# LED_Driver.net
KiCad netlist of a schematic drawn in Altium Designer
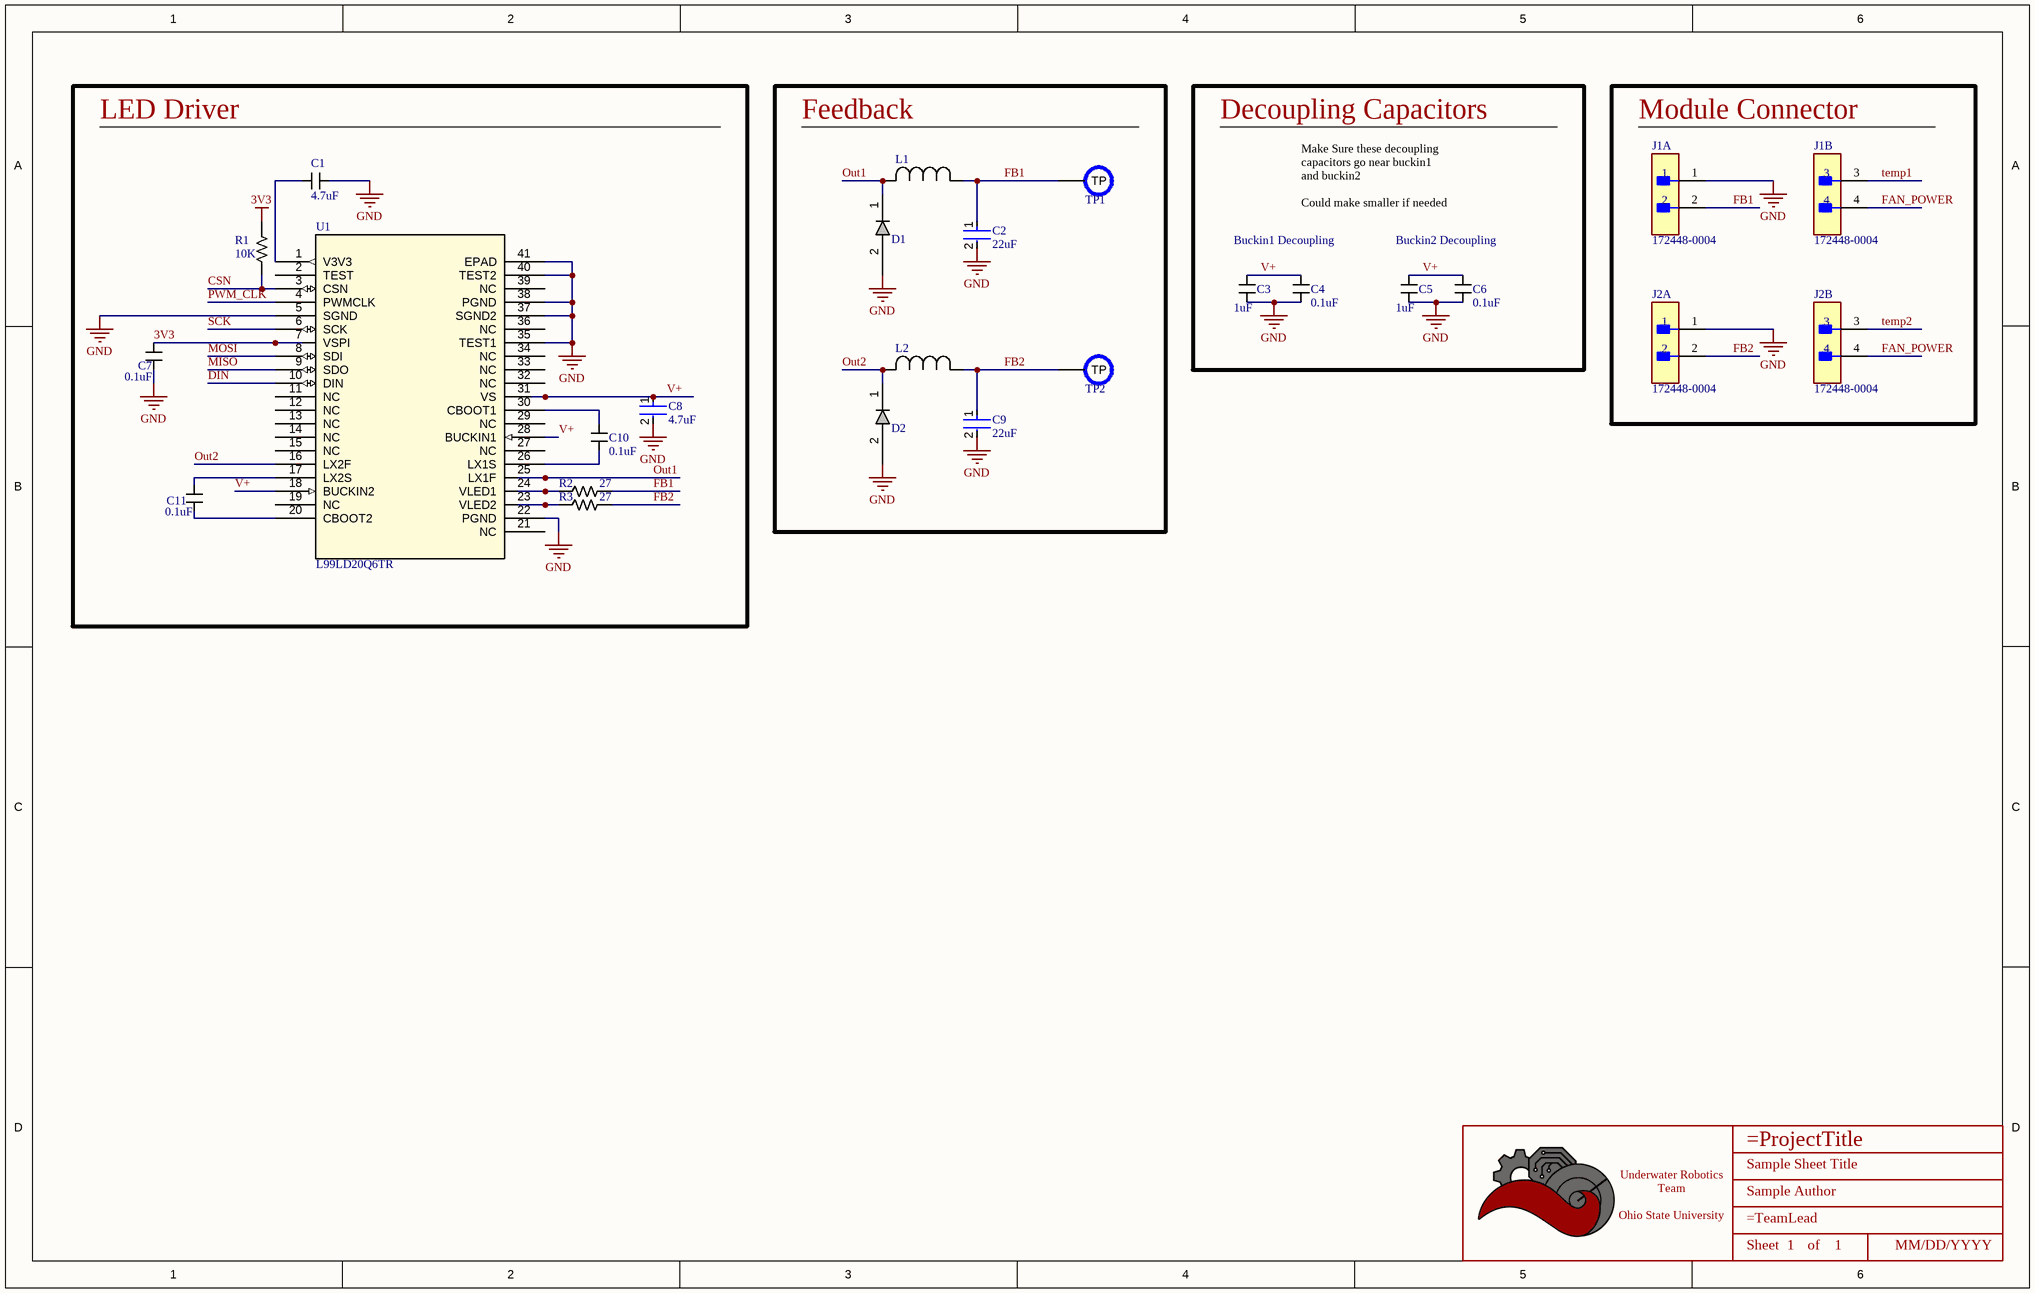
[diagram p0: LED_Driver.SchDoc]

(export (version "E")
  (design (tool "Eeschema 10.0.6"))
  (components
    (comp (ref "*")
      (value "Title_Block")
      (footprint "LOGO")
      (description "UWRT Schematic Title Block Template\r\n\r\nCreated June 2021, Dylan Trainor")
      (libsource (lib "UWRT") (part "Title_Block"))
    )
    (comp (ref "C1")
      (value "4.7uF")
      (footprint "CAPACITOR_0603")
      (description "Cap 4.7uF 6.3V +/-10%\r\nCeramic 0603")
      (fields
        (field (name "TOLERANCE") "+/- 10%")
        (field (name "VOLTAGE") "6.3V")
        (field (name "MADE BY") "Robert Pafford")
      )
      (libsource (lib "Capacitors") (part "CAPACITOR_4.7uF_0603"))
    )
    (comp (ref "C2")
      (value "22uF")
      (footprint "FP-C2012-125-0_2-MFG")
      (description "Multilayer Ceramic Capacitors 22μF ±20% 35V X5R SMD 0805")
      (fields (field (name "TOLERANCE") "20%"))
      (libsource (lib "Altium Content Vault") (part "b4654b650e69147ec39a6b967a45e02"))
    )
    (comp (ref "C3")
      (value "1uF")
      (footprint "CAPACITOR_0603")
      (description "Cap 1uF 25V +/-10%\r\nCeramic 0603")
      (fields
        (field (name "TOLERANCE") "+/- 10%")
        (field (name "VOLTAGE") "16V")
        (field (name "MADE BY") "Flip B")
      )
      (libsource (lib "Capacitors") (part "CAPACITOR_1uF_0603_25V"))
    )
    (comp (ref "C4")
      (value "0.1uF")
      (footprint "CAPACITOR_0603")
      (description "Cap 100nF 25V +/-10%\r\nCeramic 0603")
      (fields
        (field (name "TOLERANCE") "+/- 10%")
        (field (name "VOLTAGE") "6.3V")
        (field (name "MADE BY") "Flip B")
      )
      (libsource (lib "Capacitors") (part "CAPACITOR_0.1uF_0603_25V"))
    )
    (comp (ref "C5")
      (value "1uF")
      (footprint "CAPACITOR_0603")
      (description "Cap 1uF 25V +/-10%\r\nCeramic 0603")
      (fields
        (field (name "TOLERANCE") "+/- 10%")
        (field (name "VOLTAGE") "16V")
        (field (name "MADE BY") "Flip B")
      )
      (libsource (lib "Capacitors") (part "CAPACITOR_1uF_0603_25V"))
    )
    (comp (ref "C6")
      (value "0.1uF")
      (footprint "CAPACITOR_0603")
      (description "Cap 100nF 25V +/-10%\r\nCeramic 0603")
      (fields
        (field (name "TOLERANCE") "+/- 10%")
        (field (name "VOLTAGE") "6.3V")
        (field (name "MADE BY") "Flip B")
      )
      (libsource (lib "Capacitors") (part "CAPACITOR_0.1uF_0603_25V"))
    )
    (comp (ref "C7")
      (value "0.1uF")
      (footprint "CAPACITOR_0603")
      (description "Cap 100nF 6.3V +/-10%\r\nCeramic 0603")
      (fields
        (field (name "TOLERANCE") "+/- 10%")
        (field (name "VOLTAGE") "6.3V")
        (field (name "MADE BY") "Flip B")
      )
      (libsource (lib "Capacitors") (part "CAPACITOR_0.1uF_0603_1"))
    )
    (comp (ref "C8")
      (value "4.7uF")
      (footprint "CAPACITOR_0603")
      (description "Chip Multilayer Ceramic Capacitors for General Purpose, 0603, 4.7uF, X5R, 15%, 20%, 35V")
      (fields (field (name "TOLERANCE") "20%"))
      (libsource (lib "Capacitors") (part "CAP CERM 4.7UF 20% 35V"))
    )
    (comp (ref "C9")
      (value "22uF")
      (footprint "FP-C2012-125-0_2-MFG")
      (description "Multilayer Ceramic Capacitors 22μF ±20% 35V X5R SMD 0805")
      (fields (field (name "TOLERANCE") "20%"))
      (libsource (lib "Altium Content Vault") (part "b4654b650e69147ec39a6b967a45e02"))
    )
    (comp (ref "C10")
      (value "0.1uF")
      (footprint "CAPACITOR_0603")
      (description "Cap 100nF 25V +/-10%\r\nCeramic 0603")
      (fields
        (field (name "TOLERANCE") "+/- 10%")
        (field (name "VOLTAGE") "6.3V")
        (field (name "MADE BY") "Flip B")
      )
      (libsource (lib "Capacitors") (part "CAPACITOR_0.1uF_0603_25V"))
    )
    (comp (ref "C11")
      (value "0.1uF")
      (footprint "CAPACITOR_0603")
      (description "Cap 100nF 25V +/-10%\r\nCeramic 0603")
      (fields
        (field (name "TOLERANCE") "+/- 10%")
        (field (name "VOLTAGE") "6.3V")
        (field (name "MADE BY") "Flip B")
      )
      (libsource (lib "Capacitors") (part "CAPACITOR_0.1uF_0603_25V"))
    )
    (comp (ref "D1")
      (value "CCS15S40,L3F")
      (footprint "SOD-963   CST2C_TOS")
      (description "DIODE SCHOTTKY 40V 1.5A CST2C")
      (fields (field (name "COPYRIGHT") "Copyright (C) 2023 Ultra Librarian. All rights reserved."))
      (libsource (lib "Diodes") (part "SCHOTTKY_40V_1.5A"))
    )
    (comp (ref "D2")
      (value "CCS15S40,L3F")
      (footprint "SOD-963   CST2C_TOS")
      (description "DIODE SCHOTTKY 40V 1.5A CST2C")
      (fields (field (name "COPYRIGHT") "Copyright (C) 2023 Ultra Librarian. All rights reserved."))
      (libsource (lib "Diodes") (part "SCHOTTKY_40V_1.5A"))
    )
    (comp (ref "J1")
      (value "172448-0004")
      (footprint "FP-172448-0004-MFG")
      (description "172448-0004 Conn Power HDR 4 POS 4.2mm Solder RA Thru-Hole 4 Terminal 1 Port Mini-Fit Jr™ Frame")
      (libsource (lib "Altium Content Vault") (part "ac72c5313ea981db199dbd0e8237b04"))
    )
    (comp (ref "J2")
      (value "172448-0004")
      (footprint "FP-172448-0004-MFG")
      (description "172448-0004 Conn Power HDR 4 POS 4.2mm Solder RA Thru-Hole 4 Terminal 1 Port Mini-Fit Jr™ Frame")
      (libsource (lib "Altium Content Vault") (part "ac72c5313ea981db199dbd0e8237b04"))
    )
    (comp (ref "L1")
      (value "INDUCTOR_500uH")
      (footprint "IND_BOURNS_5256")
      (description "5256-RC ¦ 500 µH Unshielded Drum Core, Wirewound Inductor 2 A 260mOhm Max Axial, Through Hole")
      (libsource (lib "Inductors") (part "INDUCTOR_500uH"))
    )
    (comp (ref "L2")
      (value "INDUCTOR_500uH")
      (footprint "IND_BOURNS_5256")
      (description "5256-RC ¦ 500 µH Unshielded Drum Core, Wirewound Inductor 2 A 260mOhm Max Axial, Through Hole")
      (libsource (lib "Inductors") (part "INDUCTOR_500uH"))
    )
    (comp (ref "R1")
      (value "10k Ohm 1% 1/16W")
      (footprint "RESISTOR_0402")
      (description "RES 10k OHM 1% 1/16W 0402")
      (fields
        (field (name "TOLERANCE") "+/- 1%")
        (field (name "VALUE  (OHMS)") "10K")
        (field (name "MADE BY") "Robert Pafford")
      )
      (libsource (lib "Resistors") (part "RESISTOR_10K_0402"))
    )
    (comp (ref "R2")
      (value "27 Ohm 5% 1/8W")
      (footprint "RESISTOR_0603")
      (description "RES 27 OHM 5% 1/8W 0603")
      (fields
        (field (name "TOLERANCE") "+/- 5%")
        (field (name "VALUE  (OHMS)") "27")
        (field (name "MADE BY") "Robert Pafford")
      )
      (libsource (lib "Resistors") (part "RESISTOR_27_0603"))
    )
    (comp (ref "R3")
      (value "27 Ohm 5% 1/8W")
      (footprint "RESISTOR_0603")
      (description "RES 27 OHM 5% 1/8W 0603")
      (fields
        (field (name "TOLERANCE") "+/- 5%")
        (field (name "VALUE  (OHMS)") "27")
        (field (name "MADE BY") "Robert Pafford")
      )
      (libsource (lib "Resistors") (part "RESISTOR_27_0603"))
    )
    (comp (ref "TP1")
      (value "PCB Test Point")
      (footprint "TESTPOINT_1.2MM")
      (fields (field (name "MADE BY") "Robert Pafford"))
      (libsource (lib "Connectors") (part "TESTPOINT"))
    )
    (comp (ref "TP2")
      (value "PCB Test Point")
      (footprint "TESTPOINT_1.2MM")
      (fields (field (name "MADE BY") "Robert Pafford"))
      (libsource (lib "Connectors") (part "TESTPOINT"))
    )
    (comp (ref "U1")
      (value "L99LD20Q6TR")
      (footprint "L99LD20Q6TR")
      (description "IC LED DRVR RGLTR PWM 1.5A 40QFN")
      (fields (field (name "COPYRIGHT") "Copyright (C) 2023 Ultra Librarian. All rights reserved."))
      (libsource (lib "Integrated Circuits") (part "L99LD20Q6TR"))
    )
  )
  (nets
    (net (code "1") (name "/CSN") (class "Default")
      (node (ref "R1") (pin "2") (pinfunction "2_2") (pintype "passive"))
      (node (ref "U1") (pin "3") (pinfunction "CSN_3") (pintype "bidirectional"))
    )
    (net (code "2") (name "/DIN") (class "Default")
      (node (ref "U1") (pin "10") (pinfunction "DIN_10") (pintype "bidirectional"))
    )
    (net (code "3") (name "/FAN_POWER") (class "Default")
      (node (ref "J1") (pin "4") (pinfunction "4_4") (pintype "passive"))
      (node (ref "J2") (pin "4") (pinfunction "4_4") (pintype "passive"))
    )
    (net (code "4") (name "/FB1") (class "Default")
      (node (ref "C2") (pin "1") (pinfunction "1_1") (pintype "passive"))
      (node (ref "J1") (pin "2") (pinfunction "2_2") (pintype "passive"))
      (node (ref "L1") (pin "1") (pinfunction "1_1") (pintype "passive"))
      (node (ref "R2") (pin "1") (pinfunction "1_1") (pintype "passive"))
      (node (ref "TP1") (pin "TP") (pinfunction "TP_TP") (pintype "passive"))
    )
    (net (code "5") (name "/FB2") (class "Default")
      (node (ref "C9") (pin "1") (pinfunction "1_1") (pintype "passive"))
      (node (ref "J2") (pin "2") (pinfunction "2_2") (pintype "passive"))
      (node (ref "L2") (pin "1") (pinfunction "1_1") (pintype "passive"))
      (node (ref "R3") (pin "1") (pinfunction "1_1") (pintype "passive"))
      (node (ref "TP2") (pin "TP") (pinfunction "TP_TP") (pintype "passive"))
    )
    (net (code "6") (name "/MISO") (class "Default")
      (node (ref "U1") (pin "9") (pinfunction "SDO_9") (pintype "bidirectional"))
    )
    (net (code "7") (name "/MOSI") (class "Default")
      (node (ref "U1") (pin "8") (pinfunction "SDI_8") (pintype "bidirectional"))
    )
    (net (code "8") (name "/Out1") (class "Default")
      (node (ref "D1") (pin "1") (pinfunction "1_1") (pintype "passive"))
      (node (ref "L1") (pin "2") (pinfunction "2_2") (pintype "passive"))
      (node (ref "U1") (pin "25") (pinfunction "LX1F_25") (pintype "passive"))
    )
    (net (code "9") (name "/Out2") (class "Default")
      (node (ref "D2") (pin "1") (pinfunction "1_1") (pintype "passive"))
      (node (ref "L2") (pin "2") (pinfunction "2_2") (pintype "passive"))
      (node (ref "U1") (pin "16") (pinfunction "LX2F_16") (pintype "passive"))
    )
    (net (code "10") (name "/PWM_CLK") (class "Default")
      (node (ref "U1") (pin "4") (pinfunction "PWMCLK_4") (pintype "passive"))
    )
    (net (code "11") (name "/SCK") (class "Default")
      (node (ref "U1") (pin "6") (pinfunction "SCK_6") (pintype "bidirectional"))
    )
    (net (code "12") (name "/V+") (class "Default")
      (node (ref "C3") (pin "2") (pinfunction "2_2") (pintype "passive"))
      (node (ref "C4") (pin "1") (pinfunction "1_1") (pintype "passive"))
      (node (ref "C5") (pin "2") (pinfunction "2_2") (pintype "passive"))
      (node (ref "C6") (pin "1") (pinfunction "1_1") (pintype "passive"))
      (node (ref "C8") (pin "1") (pinfunction "1_1") (pintype "passive"))
      (node (ref "U1") (pin "18") (pinfunction "BUCKIN2_18") (pintype "input"))
      (node (ref "U1") (pin "28") (pinfunction "BUCKIN1_28") (pintype "input"))
      (node (ref "U1") (pin "31") (pinfunction "VS_31") (pintype "passive"))
    )
    (net (code "13") (name "/temp1") (class "Default")
      (node (ref "J1") (pin "3") (pinfunction "3_3") (pintype "passive"))
    )
    (net (code "14") (name "/temp2") (class "Default")
      (node (ref "J2") (pin "3") (pinfunction "3_3") (pintype "passive"))
    )
    (net (code "15") (name "3V3") (class "Default")
      (node (ref "C7") (pin "1") (pinfunction "1_1") (pintype "passive"))
      (node (ref "R1") (pin "1") (pinfunction "1_1") (pintype "passive"))
      (node (ref "U1") (pin "7") (pinfunction "VSPI_7") (pintype "passive"))
    )
    (net (code "16") (name "GND") (class "Default")
      (node (ref "C1") (pin "1") (pinfunction "1_1") (pintype "passive"))
      (node (ref "C2") (pin "2") (pinfunction "2_2") (pintype "passive"))
      (node (ref "C3") (pin "1") (pinfunction "1_1") (pintype "passive"))
      (node (ref "C4") (pin "2") (pinfunction "2_2") (pintype "passive"))
      (node (ref "C5") (pin "1") (pinfunction "1_1") (pintype "passive"))
      (node (ref "C6") (pin "2") (pinfunction "2_2") (pintype "passive"))
      (node (ref "C7") (pin "2") (pinfunction "2_2") (pintype "passive"))
      (node (ref "C8") (pin "2") (pinfunction "2_2") (pintype "passive"))
      (node (ref "C9") (pin "2") (pinfunction "2_2") (pintype "passive"))
      (node (ref "D1") (pin "2") (pinfunction "2_2") (pintype "passive"))
      (node (ref "D2") (pin "2") (pinfunction "2_2") (pintype "passive"))
      (node (ref "J1") (pin "1") (pinfunction "1_1") (pintype "passive"))
      (node (ref "J2") (pin "1") (pinfunction "1_1") (pintype "passive"))
      (node (ref "U1") (pin "22") (pinfunction "PGND_22") (pintype "power_in"))
      (node (ref "U1") (pin "35") (pinfunction "TEST1_35") (pintype "passive"))
      (node (ref "U1") (pin "37") (pinfunction "SGND2_37") (pintype "power_in"))
      (node (ref "U1") (pin "38") (pinfunction "PGND_38") (pintype "power_in"))
      (node (ref "U1") (pin "40") (pinfunction "TEST2_40") (pintype "passive"))
      (node (ref "U1") (pin "41") (pinfunction "EPAD_41") (pintype "power_in"))
      (node (ref "U1") (pin "5") (pinfunction "SGND_5") (pintype "power_in"))
    )
    (net (code "17") (name "Net-(U1-CBOOT1)") (class "Default")
      (node (ref "C10") (pin "1") (pinfunction "1_1") (pintype "passive"))
      (node (ref "U1") (pin "30") (pinfunction "CBOOT1_30") (pintype "passive"))
    )
    (net (code "18") (name "Net-(U1-CBOOT2)") (class "Default")
      (node (ref "C11") (pin "2") (pinfunction "2_2") (pintype "passive"))
      (node (ref "U1") (pin "20") (pinfunction "CBOOT2_20") (pintype "passive"))
    )
    (net (code "19") (name "Net-(U1-LX1S)") (class "Default")
      (node (ref "C10") (pin "2") (pinfunction "2_2") (pintype "passive"))
      (node (ref "U1") (pin "26") (pinfunction "LX1S_26") (pintype "passive"))
    )
    (net (code "20") (name "Net-(U1-LX2S)") (class "Default")
      (node (ref "C11") (pin "1") (pinfunction "1_1") (pintype "passive"))
      (node (ref "U1") (pin "17") (pinfunction "LX2S_17") (pintype "passive"))
    )
    (net (code "21") (name "Net-(U1-V3V3)") (class "Default")
      (node (ref "C1") (pin "2") (pinfunction "2_2") (pintype "passive"))
      (node (ref "U1") (pin "1") (pinfunction "V3V3_1") (pintype "output"))
    )
    (net (code "22") (name "Net-(U1-VLED1)") (class "Default")
      (node (ref "R2") (pin "2") (pinfunction "2_2") (pintype "passive"))
      (node (ref "U1") (pin "24") (pinfunction "VLED1_24") (pintype "passive"))
    )
    (net (code "23") (name "Net-(U1-VLED2)") (class "Default")
      (node (ref "R3") (pin "2") (pinfunction "2_2") (pintype "passive"))
      (node (ref "U1") (pin "23") (pinfunction "VLED2_23") (pintype "passive"))
    )
    (net (code "24") (name "unconnected-(U1-NC-Pad11)") (class "Default")
      (node (ref "U1") (pin "11") (pinfunction "NC_11") (pintype "passive"))
    )
    (net (code "25") (name "unconnected-(U1-NC-Pad12)") (class "Default")
      (node (ref "U1") (pin "12") (pinfunction "NC_12") (pintype "passive"))
    )
    (net (code "26") (name "unconnected-(U1-NC-Pad13)") (class "Default")
      (node (ref "U1") (pin "13") (pinfunction "NC_13") (pintype "passive"))
    )
    (net (code "27") (name "unconnected-(U1-NC-Pad14)") (class "Default")
      (node (ref "U1") (pin "14") (pinfunction "NC_14") (pintype "passive"))
    )
    (net (code "28") (name "unconnected-(U1-NC-Pad15)") (class "Default")
      (node (ref "U1") (pin "15") (pinfunction "NC_15") (pintype "passive"))
    )
    (net (code "29") (name "unconnected-(U1-NC-Pad19)") (class "Default")
      (node (ref "U1") (pin "19") (pinfunction "NC_19") (pintype "passive"))
    )
    (net (code "30") (name "unconnected-(U1-NC-Pad21)") (class "Default")
      (node (ref "U1") (pin "21") (pinfunction "NC_21") (pintype "passive"))
    )
    (net (code "31") (name "unconnected-(U1-NC-Pad27)") (class "Default")
      (node (ref "U1") (pin "27") (pinfunction "NC_27") (pintype "passive"))
    )
    (net (code "32") (name "unconnected-(U1-NC-Pad29)") (class "Default")
      (node (ref "U1") (pin "29") (pinfunction "NC_29") (pintype "passive"))
    )
    (net (code "33") (name "unconnected-(U1-NC-Pad32)") (class "Default")
      (node (ref "U1") (pin "32") (pinfunction "NC_32") (pintype "passive"))
    )
    (net (code "34") (name "unconnected-(U1-NC-Pad33)") (class "Default")
      (node (ref "U1") (pin "33") (pinfunction "NC_33") (pintype "passive"))
    )
    (net (code "35") (name "unconnected-(U1-NC-Pad34)") (class "Default")
      (node (ref "U1") (pin "34") (pinfunction "NC_34") (pintype "passive"))
    )
    (net (code "36") (name "unconnected-(U1-NC-Pad36)") (class "Default")
      (node (ref "U1") (pin "36") (pinfunction "NC_36") (pintype "passive"))
    )
    (net (code "37") (name "unconnected-(U1-NC-Pad39)") (class "Default")
      (node (ref "U1") (pin "39") (pinfunction "NC_39") (pintype "passive"))
    )
    (net (code "38") (name "unconnected-(U1-TEST-Pad2)") (class "Default")
      (node (ref "U1") (pin "2") (pinfunction "TEST_2") (pintype "passive"))
    )
  )
)
